# fader.net
KiCad netlist of a schematic drawn in Altium Designer
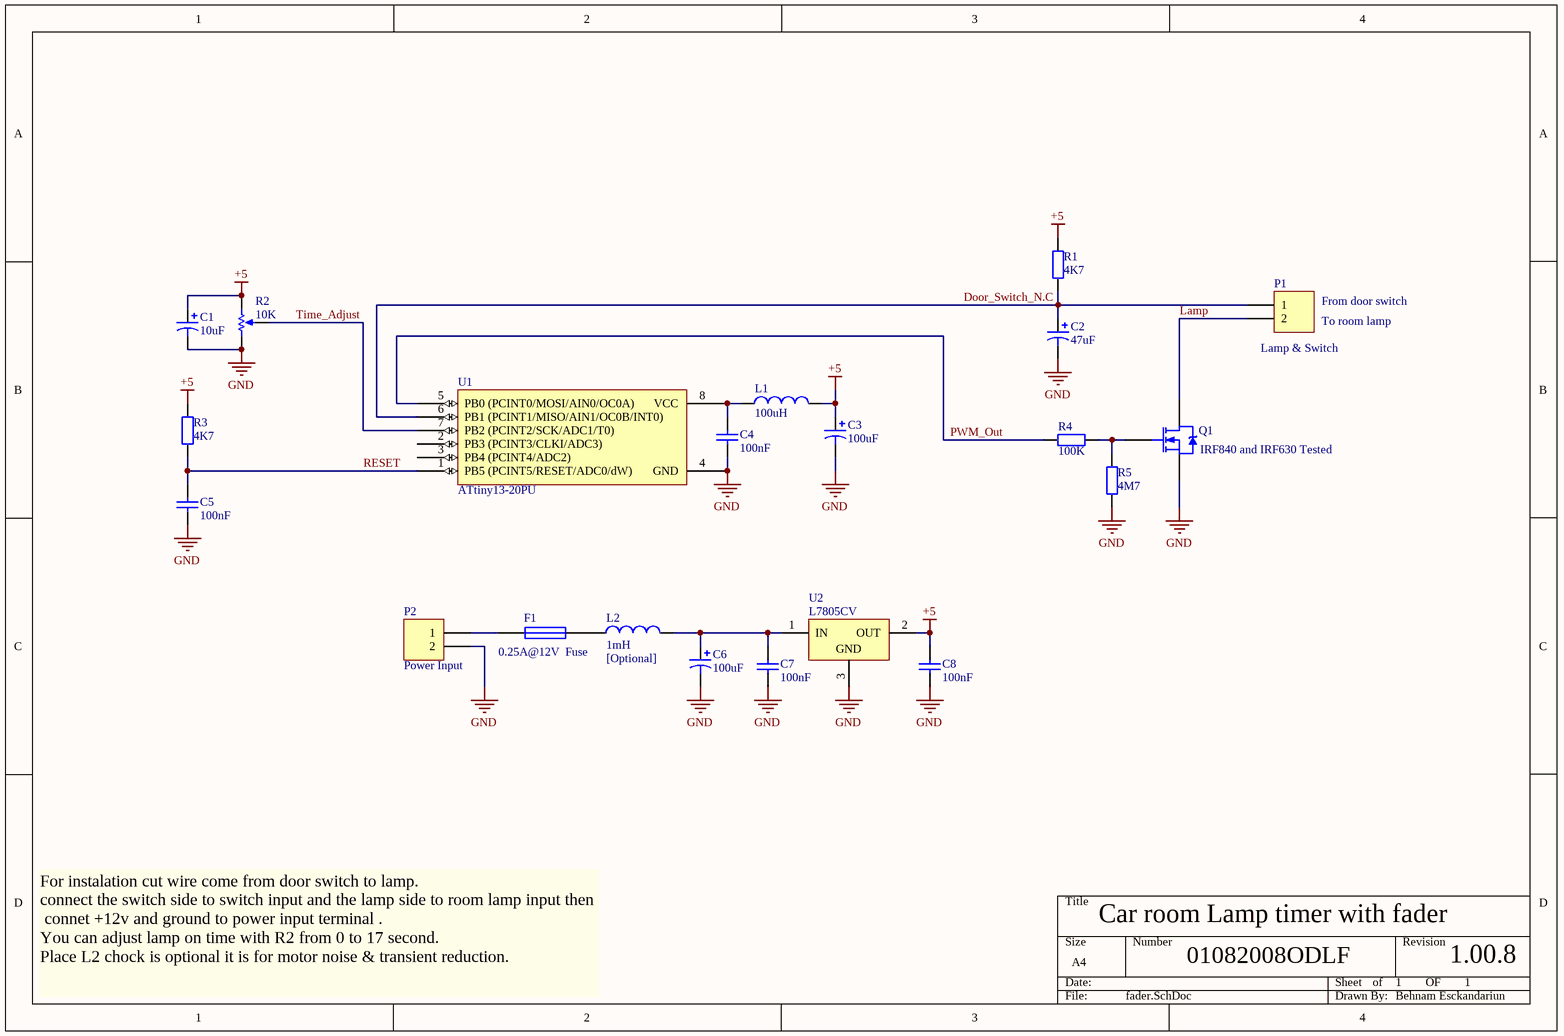
[diagram p0: fader.SchDoc]

(export (version "E")
  (design (tool "Eeschema 10.0.6"))
  (components
    (comp (ref "C1")
      (value "10uF")
      (footprint "CAPPR2-5X6.8")
      (description "Polarized Capacitor (Radial)")
      (fields (field (name "Comment") "Cap Pol1") (field (name "PUBLISHER") "Altium Limited"))
      (libsource (lib "Miscellaneous Devices") (part "Cap Pol1"))
    )
    (comp (ref "C2")
      (value "47uF")
      (footprint "CAPPR2-5X6.8")
      (description "Polarized Capacitor (Radial)")
      (fields (field (name "Comment") "Cap Pol1") (field (name "PUBLISHER") "Altium Limited"))
      (libsource (lib "Miscellaneous Devices") (part "Cap Pol1"))
    )
    (comp (ref "C3")
      (value "100uF")
      (footprint "CAPPR2-5X6.8")
      (description "Polarized Capacitor (Radial)")
      (fields (field (name "Comment") "Cap Pol1") (field (name "PUBLISHER") "Altium Limited"))
      (libsource (lib "Miscellaneous Devices") (part "Cap Pol1"))
    )
    (comp (ref "C4")
      (value "100nF")
      (footprint "rad-0.1")
      (description "Capacitor")
      (fields (field (name "Comment") "Cap") (field (name "PUBLISHER") "Altium Limited"))
      (libsource (lib "Miscellaneous Devices") (part "Cap"))
    )
    (comp (ref "C5")
      (value "100nF")
      (footprint "rad-0.1")
      (description "Capacitor")
      (fields (field (name "Comment") "Cap") (field (name "PUBLISHER") "Altium Limited"))
      (libsource (lib "Miscellaneous Devices") (part "Cap"))
    )
    (comp (ref "C6")
      (value "100uF")
      (footprint "CAPPR2-5X6.8")
      (description "Polarized Capacitor (Radial)")
      (fields (field (name "Comment") "Cap Pol1") (field (name "PUBLISHER") "Altium Limited"))
      (libsource (lib "Miscellaneous Devices") (part "Cap Pol1"))
    )
    (comp (ref "C7")
      (value "100nF")
      (footprint "rad-0.1")
      (description "Capacitor")
      (fields (field (name "Comment") "Cap") (field (name "PUBLISHER") "Altium Limited"))
      (libsource (lib "Miscellaneous Devices") (part "Cap"))
    )
    (comp (ref "C8")
      (value "100nF")
      (footprint "rad-0.1")
      (description "Capacitor")
      (fields (field (name "Comment") "Cap") (field (name "PUBLISHER") "Altium Limited"))
      (libsource (lib "Miscellaneous Devices") (part "Cap"))
    )
    (comp (ref "F1")
      (value "0.25A@12V  Fuse")
      (footprint "AXIAL-0.4")
      (description "Fuse")
      (fields (field (name "PUBLISHER") "Altium Limited"))
      (libsource (lib "Miscellaneous Devices") (part "Fuse 1"))
    )
    (comp (ref "L1")
      (value "100uH")
      (footprint "axial-0.4")
      (description "Inductor")
      (fields (field (name "PUBLISHER") "Altium Limited"))
      (libsource (lib "Miscellaneous Devices") (part "Inductor"))
    )
    (comp (ref "L2")
      (value "[Optional]")
      (footprint "axial-0.3")
      (description "Inductor")
      (fields (field (name "ALTIUM_VALUE") "1mH") (field (name "PUBLISHER") "Altium Limited"))
      (libsource (lib "Miscellaneous Devices") (part "Inductor"))
    )
    (comp (ref "P1")
      (value "Lamp & Switch")
      (footprint "Cannector-2")
      (description "Header, 2-Pin")
      (fields (field (name "PUBLISHER") "Altium Limited"))
      (libsource (lib "Miscellaneous Connectors") (part "Header 2"))
    )
    (comp (ref "P2")
      (value "Power Input")
      (footprint "Cannector-2")
      (description "Header, 2-Pin")
      (fields (field (name "PUBLISHER") "Altium Limited"))
      (libsource (lib "") (part "Header 2_1"))
    )
    (comp (ref "Q1")
      (value "IRF840 and IRF630 Tested")
      (footprint "TO-220AB")
      (description "HEXFET N-Channel Power MOSFET")
      (fields (field (name "PUBLISHER") "Altium Limited"))
      (libsource (lib "IR Discrete MOSFET - Power") (part "IRF840"))
    )
    (comp (ref "R1")
      (value "4K7")
      (footprint "AXIAL-0.4")
      (description "Resistor")
      (fields (field (name "Comment") "Res2") (field (name "PUBLISHER") "Altium Limited"))
      (libsource (lib "Miscellaneous Devices") (part "Res2"))
    )
    (comp (ref "R2")
      (value "10K")
      (footprint "VR4")
      (description "Potentiometer")
      (fields (field (name "Comment") "RPot") (field (name "PUBLISHER") "Altium Limited"))
      (libsource (lib "Miscellaneous Devices") (part "RPot"))
    )
    (comp (ref "R3")
      (value "4K7")
      (footprint "AXIAL-0.4")
      (description "Resistor")
      (fields (field (name "Comment") "Res2") (field (name "PUBLISHER") "Altium Limited"))
      (libsource (lib "Miscellaneous Devices") (part "Res2"))
    )
    (comp (ref "R4")
      (value "100K")
      (footprint "AXIAL-0.4")
      (description "Resistor")
      (fields (field (name "Comment") "Res2") (field (name "PUBLISHER") "Altium Limited"))
      (libsource (lib "") (part "Res2_1"))
    )
    (comp (ref "R5")
      (value "4M7")
      (footprint "AXIAL-0.4")
      (description "Resistor")
      (fields (field (name "Comment") "Res2") (field (name "PUBLISHER") "Altium Limited"))
      (libsource (lib "") (part "Res2_2"))
    )
    (comp (ref "U1")
      (value "ATtiny13-20PU")
      (footprint "DIP-8")
      (description "Atmel AVR 8-Bit Microcontroller")
      (libsource (lib "Atmel Microcontroller 8-Bit AVR") (part "ATtiny13-20PI"))
    )
    (comp (ref "U2")
      (value "L7805CV")
      (footprint "TO220ABN")
      (description "Positive Voltage Regulator")
      (fields (field (name "PUBLISHER") "Altium Limited"))
      (libsource (lib "ST Power Mgt Voltage Regulator") (part "L7805CV"))
    )
  )
  (nets
    (net (code "1") (name "+5") (class "Default")
      (node (ref "C1") (pin "1") (pinfunction "1_1") (pintype "passive"))
      (node (ref "C3") (pin "1") (pinfunction "1_1") (pintype "passive"))
      (node (ref "C8") (pin "1") (pinfunction "1_1") (pintype "passive"))
      (node (ref "L1") (pin "2") (pinfunction "2_2") (pintype "passive"))
      (node (ref "R1") (pin "2") (pinfunction "2_2") (pintype "passive"))
      (node (ref "R2") (pin "2") (pinfunction "BOT_2") (pintype "passive"))
      (node (ref "R3") (pin "2") (pinfunction "2_2") (pintype "passive"))
      (node (ref "U2") (pin "2") (pinfunction "OUT_2") (pintype "power_in"))
    )
    (net (code "2") (name "/Door_Switch_N.C") (class "Default")
      (node (ref "C2") (pin "1") (pinfunction "1_1") (pintype "passive"))
      (node (ref "P1") (pin "1") (pinfunction "1_1") (pintype "passive"))
      (node (ref "R1") (pin "1") (pinfunction "1_1") (pintype "passive"))
      (node (ref "U1") (pin "6") (pinfunction "PB1_(PCINT1/MISO/AIN1/OC0B/INT0)_6") (pintype "bidirectional"))
    )
    (net (code "3") (name "/Lamp") (class "Default")
      (node (ref "P1") (pin "2") (pinfunction "2_2") (pintype "passive"))
      (node (ref "Q1") (pin "2") (pinfunction "D_2") (pintype "passive"))
    )
    (net (code "4") (name "/PWM_Out") (class "Default")
      (node (ref "R4") (pin "2") (pinfunction "2_2") (pintype "passive"))
      (node (ref "U1") (pin "5") (pinfunction "PB0_(PCINT0/MOSI/AIN0/OC0A)_5") (pintype "bidirectional"))
    )
    (net (code "5") (name "/RESET") (class "Default")
      (node (ref "C5") (pin "1") (pinfunction "1_1") (pintype "passive"))
      (node (ref "R3") (pin "1") (pinfunction "1_1") (pintype "passive"))
      (node (ref "U1") (pin "1") (pinfunction "PB5_(PCINT5/RESET/ADC0/dW)_1") (pintype "bidirectional"))
    )
    (net (code "6") (name "/Time_Adjust") (class "Default")
      (node (ref "R2") (pin "3") (pinfunction "TAP_3") (pintype "passive"))
      (node (ref "U1") (pin "7") (pinfunction "PB2_(PCINT2/SCK/ADC1/T0)_7") (pintype "bidirectional"))
    )
    (net (code "7") (name "GND") (class "Default")
      (node (ref "C1") (pin "2") (pinfunction "2_2") (pintype "passive"))
      (node (ref "C2") (pin "2") (pinfunction "2_2") (pintype "passive"))
      (node (ref "C3") (pin "2") (pinfunction "2_2") (pintype "passive"))
      (node (ref "C4") (pin "2") (pinfunction "2_2") (pintype "passive"))
      (node (ref "C5") (pin "2") (pinfunction "2_2") (pintype "passive"))
      (node (ref "C6") (pin "2") (pinfunction "2_2") (pintype "passive"))
      (node (ref "C7") (pin "2") (pinfunction "2_2") (pintype "passive"))
      (node (ref "C8") (pin "2") (pinfunction "2_2") (pintype "passive"))
      (node (ref "P2") (pin "2") (pinfunction "2_2") (pintype "passive"))
      (node (ref "Q1") (pin "3") (pinfunction "S_3") (pintype "passive"))
      (node (ref "R2") (pin "1") (pinfunction "TOP_1") (pintype "passive"))
      (node (ref "R5") (pin "2") (pinfunction "2_2") (pintype "passive"))
      (node (ref "U1") (pin "4") (pinfunction "GND_4") (pintype "power_in"))
      (node (ref "U2") (pin "3") (pinfunction "GND_3") (pintype "power_in"))
    )
    (net (code "8") (name "Net-(F1-Pad1)") (class "Default")
      (node (ref "F1") (pin "1") (pinfunction "1_1") (pintype "passive"))
      (node (ref "P2") (pin "1") (pinfunction "1_1") (pintype "passive"))
    )
    (net (code "9") (name "Net-(F1-Pad2)") (class "Default")
      (node (ref "F1") (pin "2") (pinfunction "2_2") (pintype "passive"))
      (node (ref "L2") (pin "1") (pinfunction "1_1") (pintype "passive"))
    )
    (net (code "10") (name "Net-(Q1-G)") (class "Default")
      (node (ref "Q1") (pin "1") (pinfunction "G_1") (pintype "passive"))
      (node (ref "R4") (pin "1") (pinfunction "1_1") (pintype "passive"))
      (node (ref "R5") (pin "1") (pinfunction "1_1") (pintype "passive"))
    )
    (net (code "11") (name "Net-(U1-VCC)") (class "Default")
      (node (ref "C4") (pin "1") (pinfunction "1_1") (pintype "passive"))
      (node (ref "L1") (pin "1") (pinfunction "1_1") (pintype "passive"))
      (node (ref "U1") (pin "8") (pinfunction "VCC_8") (pintype "power_in"))
    )
    (net (code "12") (name "Net-(U2-IN)") (class "Default")
      (node (ref "C6") (pin "1") (pinfunction "1_1") (pintype "passive"))
      (node (ref "C7") (pin "1") (pinfunction "1_1") (pintype "passive"))
      (node (ref "L2") (pin "2") (pinfunction "2_2") (pintype "passive"))
      (node (ref "U2") (pin "1") (pinfunction "IN_1") (pintype "power_in"))
    )
    (net (code "13") (name "unconnected-(U1-PB3_(PCINT3{slash}CLKI{slash}ADC3)-Pad2)") (class "Default")
      (node (ref "U1") (pin "2") (pinfunction "PB3_(PCINT3/CLKI/ADC3)_2") (pintype "bidirectional"))
    )
    (net (code "14") (name "unconnected-(U1-PB4_(PCINT4{slash}ADC2)-Pad3)") (class "Default")
      (node (ref "U1") (pin "3") (pinfunction "PB4_(PCINT4/ADC2)_3") (pintype "bidirectional"))
    )
  )
)
